# tubeboard.net
KiCad netlist of a schematic drawn in EAGLE
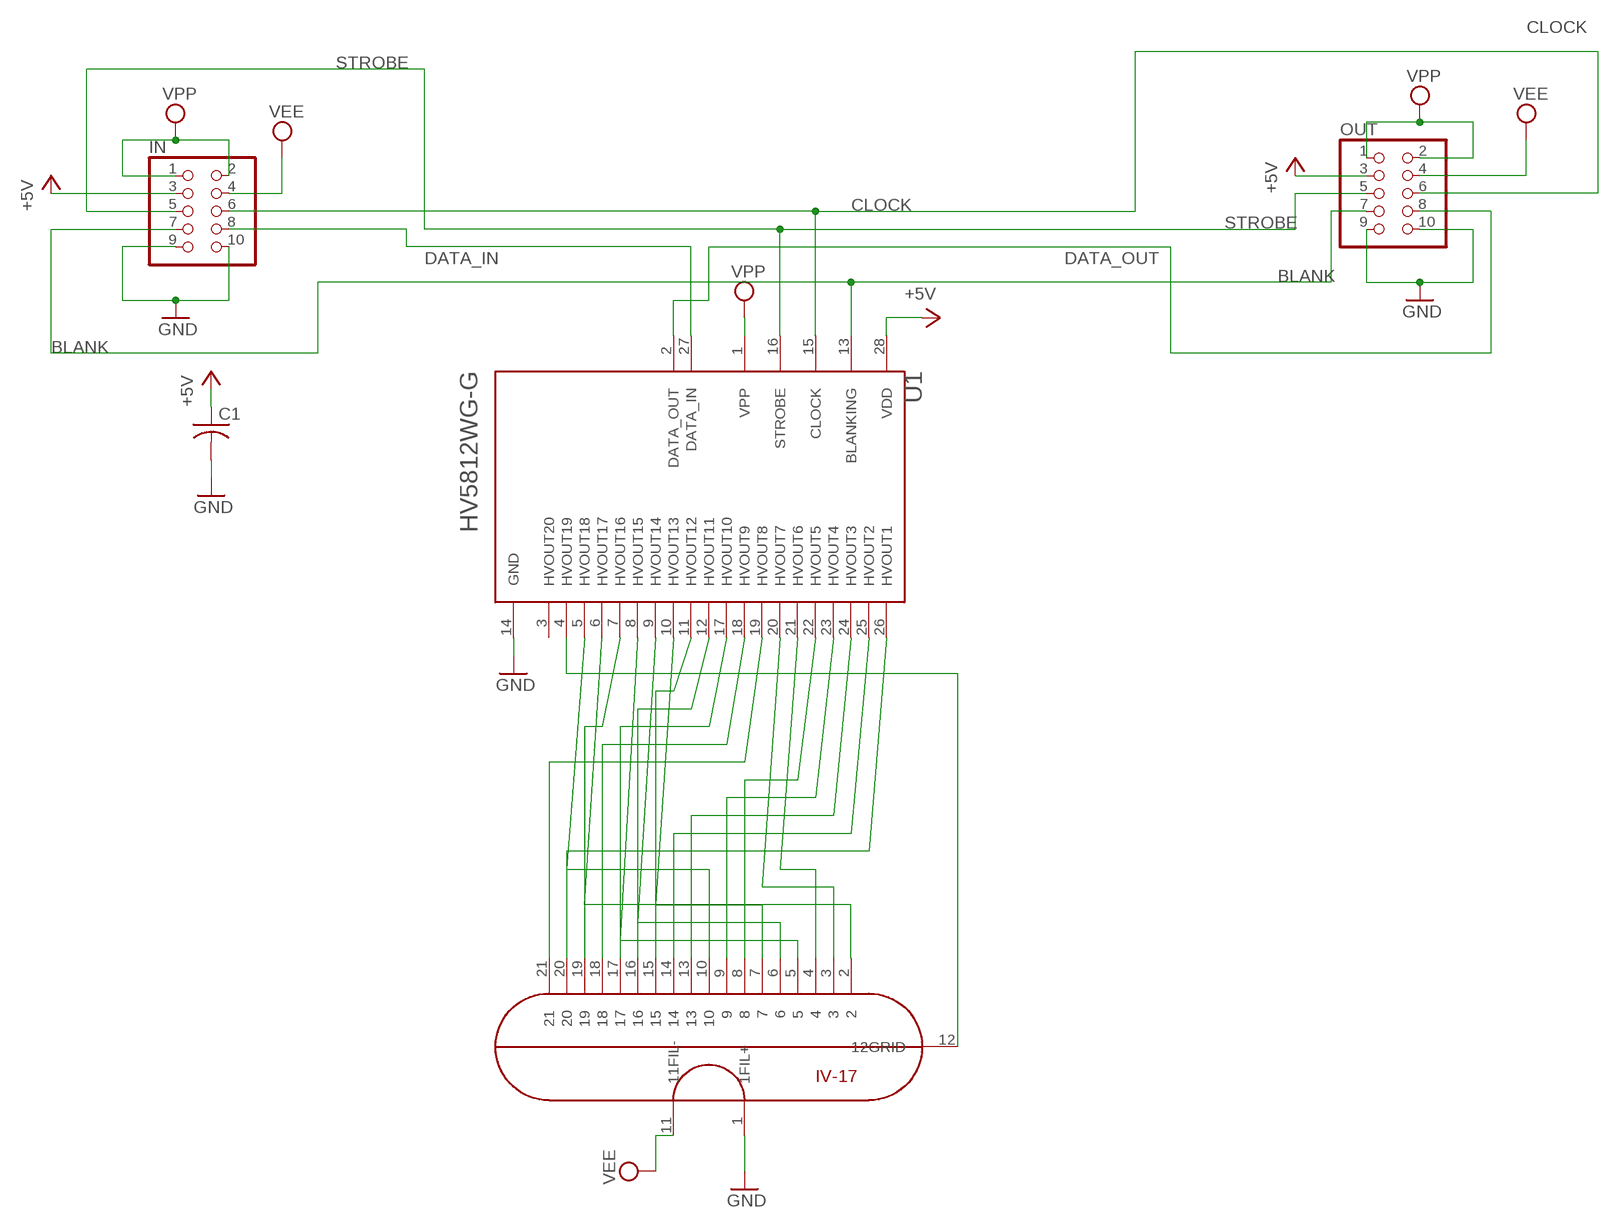
[diagram p0: schematic, sheet 1]

(export (version "E")
  (design (tool "Eeschema 10.0.6"))
  (components
    (comp (ref "C1")
      (value "C-USC0805")
      (footprint "eagle-import:C0805")
      (libsource (lib "eagle-import") (part "C-USC0805"))
    )
    (comp (ref "IN")
      (value "PINHD-2X5/90")
      (footprint "eagle-import:2X05_90")
      (libsource (lib "eagle-import") (part "PINHD-2X5/90"))
    )
    (comp (ref "IV17")
      (value "IV17")
      (footprint "eagle-import:NIXIE-22")
      (libsource (lib "eagle-import") (part "IV17"))
    )
    (comp (ref "OUT")
      (value "PINHD-2X5/90")
      (footprint "eagle-import:2X05_90")
      (libsource (lib "eagle-import") (part "PINHD-2X5/90"))
    )
    (comp (ref "U1")
      (value "MICROCHIP_HV5812WG-GMICROCHIP_HV5812WG-G_0_0")
      (footprint "eagle-import:MICROCHIP_HV5812WG-G_0")
      (fields
        (field (name "DIGIKEY_PART_NUMBER") "HV5812WG-GCT-ND")
        (field (name "MF") "Microchip")
        (field (name "MOUSER_PART_NUMBER") "689-HV5812WG-G")
      )
      (libsource (lib "eagle-import") (part "MICROCHIP_HV5812WG-GMICROCHIP_HV5812WG-G_0_0"))
    )
  )
  (nets
    (net (code "1") (name "+5V") (class "Default")
      (node (ref "C1") (pin "1") (pinfunction "1_1") (pintype "passive"))
      (node (ref "IN") (pin "3") (pinfunction "3_3") (pintype "passive"))
      (node (ref "OUT") (pin "3") (pinfunction "3_3") (pintype "passive"))
      (node (ref "U1") (pin "28") (pinfunction "VDD_28") (pintype "bidirectional"))
    )
    (net (code "2") (name "/BLANK") (class "Default")
      (node (ref "IN") (pin "7") (pinfunction "7_7") (pintype "passive"))
      (node (ref "OUT") (pin "7") (pinfunction "7_7") (pintype "passive"))
      (node (ref "U1") (pin "13") (pinfunction "BLANKING_13") (pintype "bidirectional"))
    )
    (net (code "3") (name "/CLOCK") (class "Default")
      (node (ref "IN") (pin "6") (pinfunction "6_6") (pintype "passive"))
      (node (ref "OUT") (pin "6") (pinfunction "6_6") (pintype "passive"))
      (node (ref "U1") (pin "15") (pinfunction "CLOCK_15") (pintype "bidirectional"))
    )
    (net (code "4") (name "/DATA_IN") (class "Default")
      (node (ref "IN") (pin "8") (pinfunction "8_8") (pintype "passive"))
      (node (ref "U1") (pin "27") (pinfunction "DATA_IN_27") (pintype "bidirectional"))
    )
    (net (code "5") (name "/DATA_OUT") (class "Default")
      (node (ref "OUT") (pin "8") (pinfunction "8_8") (pintype "passive"))
      (node (ref "U1") (pin "2") (pinfunction "DATA_OUT_2") (pintype "bidirectional"))
    )
    (net (code "6") (name "/STROBE") (class "Default")
      (node (ref "IN") (pin "5") (pinfunction "5_5") (pintype "passive"))
      (node (ref "OUT") (pin "5") (pinfunction "5_5") (pintype "passive"))
      (node (ref "U1") (pin "16") (pinfunction "STROBE_16") (pintype "bidirectional"))
    )
    (net (code "7") (name "GND") (class "Default")
      (node (ref "C1") (pin "2") (pinfunction "2_2") (pintype "passive"))
      (node (ref "IN") (pin "10") (pinfunction "10_10") (pintype "passive"))
      (node (ref "IN") (pin "9") (pinfunction "9_9") (pintype "passive"))
      (node (ref "IV17") (pin "1") (pinfunction "1FIL+_1") (pintype "bidirectional"))
      (node (ref "OUT") (pin "10") (pinfunction "10_10") (pintype "passive"))
      (node (ref "OUT") (pin "9") (pinfunction "9_9") (pintype "passive"))
      (node (ref "U1") (pin "14") (pinfunction "GND_14") (pintype "bidirectional"))
    )
    (net (code "8") (name "Net-(IV17-12GRID)") (class "Default")
      (node (ref "IV17") (pin "12") (pinfunction "12GRID_12") (pintype "bidirectional"))
      (node (ref "U1") (pin "4") (pinfunction "HVOUT19_4") (pintype "bidirectional"))
    )
    (net (code "9") (name "Net-(U1-HVOUT1)") (class "Default")
      (node (ref "IV17") (pin "20") (pinfunction "20_20") (pintype "bidirectional"))
      (node (ref "U1") (pin "26") (pinfunction "HVOUT1_26") (pintype "bidirectional"))
    )
    (net (code "10") (name "Net-(U1-HVOUT2)") (class "Default")
      (node (ref "IV17") (pin "14") (pinfunction "14_14") (pintype "bidirectional"))
      (node (ref "U1") (pin "25") (pinfunction "HVOUT2_25") (pintype "bidirectional"))
    )
    (net (code "11") (name "Net-(U1-HVOUT3)") (class "Default")
      (node (ref "IV17") (pin "13") (pinfunction "13_13") (pintype "bidirectional"))
      (node (ref "U1") (pin "24") (pinfunction "HVOUT3_24") (pintype "bidirectional"))
    )
    (net (code "12") (name "Net-(U1-HVOUT4)") (class "Default")
      (node (ref "IV17") (pin "9") (pinfunction "9_9") (pintype "bidirectional"))
      (node (ref "U1") (pin "23") (pinfunction "HVOUT4_23") (pintype "bidirectional"))
    )
    (net (code "13") (name "Net-(U1-HVOUT5)") (class "Default")
      (node (ref "IV17") (pin "8") (pinfunction "8_8") (pintype "bidirectional"))
      (node (ref "U1") (pin "22") (pinfunction "HVOUT5_22") (pintype "bidirectional"))
    )
    (net (code "14") (name "Net-(U1-HVOUT6)") (class "Default")
      (node (ref "IV17") (pin "4") (pinfunction "4_4") (pintype "bidirectional"))
      (node (ref "U1") (pin "21") (pinfunction "HVOUT6_21") (pintype "bidirectional"))
    )
    (net (code "15") (name "Net-(U1-HVOUT7)") (class "Default")
      (node (ref "IV17") (pin "3") (pinfunction "3_3") (pintype "bidirectional"))
      (node (ref "U1") (pin "20") (pinfunction "HVOUT7_20") (pintype "bidirectional"))
    )
    (net (code "16") (name "Net-(U1-HVOUT8)") (class "Default")
      (node (ref "IV17") (pin "21") (pinfunction "21_21") (pintype "bidirectional"))
      (node (ref "U1") (pin "19") (pinfunction "HVOUT8_19") (pintype "bidirectional"))
    )
    (net (code "17") (name "Net-(U1-HVOUT9)") (class "Default")
      (node (ref "IV17") (pin "18") (pinfunction "18_18") (pintype "bidirectional"))
      (node (ref "U1") (pin "18") (pinfunction "HVOUT9_18") (pintype "bidirectional"))
    )
    (net (code "18") (name "Net-(U1-HVOUT10)") (class "Default")
      (node (ref "IV17") (pin "17") (pinfunction "17_17") (pintype "bidirectional"))
      (node (ref "U1") (pin "17") (pinfunction "HVOUT10_17") (pintype "bidirectional"))
    )
    (net (code "19") (name "Net-(U1-HVOUT11)") (class "Default")
      (node (ref "IV17") (pin "16") (pinfunction "16_16") (pintype "bidirectional"))
      (node (ref "U1") (pin "12") (pinfunction "HVOUT11_12") (pintype "bidirectional"))
    )
    (net (code "20") (name "Net-(U1-HVOUT12)") (class "Default")
      (node (ref "IV17") (pin "15") (pinfunction "15_15") (pintype "bidirectional"))
      (node (ref "U1") (pin "11") (pinfunction "HVOUT12_11") (pintype "bidirectional"))
    )
    (net (code "21") (name "Net-(U1-HVOUT13)") (class "Default")
      (node (ref "IV17") (pin "7") (pinfunction "7_7") (pintype "bidirectional"))
      (node (ref "U1") (pin "10") (pinfunction "HVOUT13_10") (pintype "bidirectional"))
    )
    (net (code "22") (name "Net-(U1-HVOUT14)") (class "Default")
      (node (ref "IV17") (pin "6") (pinfunction "6_6") (pintype "bidirectional"))
      (node (ref "U1") (pin "9") (pinfunction "HVOUT14_9") (pintype "bidirectional"))
    )
    (net (code "23") (name "Net-(U1-HVOUT15)") (class "Default")
      (node (ref "IV17") (pin "5") (pinfunction "5_5") (pintype "bidirectional"))
      (node (ref "U1") (pin "8") (pinfunction "HVOUT15_8") (pintype "bidirectional"))
    )
    (net (code "24") (name "Net-(U1-HVOUT16)") (class "Default")
      (node (ref "IV17") (pin "19") (pinfunction "19_19") (pintype "bidirectional"))
      (node (ref "U1") (pin "7") (pinfunction "HVOUT16_7") (pintype "bidirectional"))
    )
    (net (code "25") (name "Net-(U1-HVOUT17)") (class "Default")
      (node (ref "IV17") (pin "2") (pinfunction "2_2") (pintype "bidirectional"))
      (node (ref "U1") (pin "6") (pinfunction "HVOUT17_6") (pintype "bidirectional"))
    )
    (net (code "26") (name "Net-(U1-HVOUT18)") (class "Default")
      (node (ref "IV17") (pin "10") (pinfunction "10_10") (pintype "bidirectional"))
      (node (ref "U1") (pin "5") (pinfunction "HVOUT18_5") (pintype "bidirectional"))
    )
    (net (code "27") (name "VEE") (class "Default")
      (node (ref "IN") (pin "4") (pinfunction "4_4") (pintype "passive"))
      (node (ref "IV17") (pin "11") (pinfunction "11FIL-_11") (pintype "bidirectional"))
      (node (ref "OUT") (pin "4") (pinfunction "4_4") (pintype "passive"))
    )
    (net (code "28") (name "VPP") (class "Default")
      (node (ref "IN") (pin "1") (pinfunction "1_1") (pintype "passive"))
      (node (ref "IN") (pin "2") (pinfunction "2_2") (pintype "passive"))
      (node (ref "OUT") (pin "1") (pinfunction "1_1") (pintype "passive"))
      (node (ref "OUT") (pin "2") (pinfunction "2_2") (pintype "passive"))
      (node (ref "U1") (pin "1") (pinfunction "VPP_1") (pintype "bidirectional"))
    )
    (net (code "29") (name "unconnected-(U1-HVOUT20-Pad3)") (class "Default")
      (node (ref "U1") (pin "3") (pinfunction "HVOUT20_3") (pintype "bidirectional"))
    )
  )
)
